# ILI9488_touch_breakout.net
KiCad netlist of a schematic drawn in EAGLE
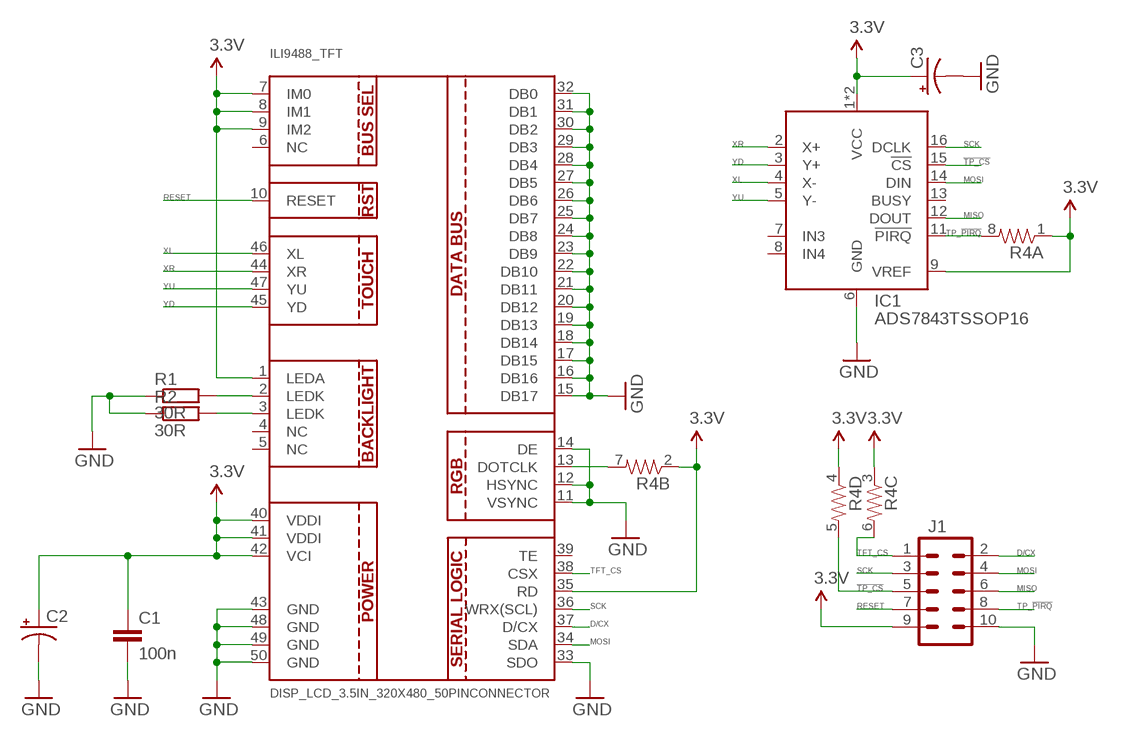
[diagram p0: schematic, sheet 1]

(export (version "E")
  (design (tool "Eeschema 10.0.6"))
  (components
    (comp (ref "C1")
      (value "100n")
      (footprint "eagle-import:C0805K")
      (libsource (lib "eagle-import") (part "C-EUC0805K"))
    )
    (comp (ref "C2")
      (value "CAPACITOR-POL0805")
      (footprint "eagle-import:0805A")
      (libsource (lib "eagle-import") (part "CAPACITOR-POL0805"))
    )
    (comp (ref "C3")
      (value "CAPACITOR-POL0805")
      (footprint "eagle-import:0805A")
      (libsource (lib "eagle-import") (part "CAPACITOR-POL0805"))
    )
    (comp (ref "IC1")
      (value "ADS7843TSSOP16")
      (footprint "eagle-import:TSSOP16")
      (libsource (lib "eagle-import") (part "ADS7843TSSOP16"))
    )
    (comp (ref "ILI9488_TFT")
      (value "DISP_LCD_3.5IN_320X480_50PINCONNECTOR")
      (footprint "eagle-import:TFT_3.5IN_50PIN_CONNECTOR")
      (libsource (lib "eagle-import") (part "DISP_LCD_3.5IN_320X480_50PINCONNECTOR"))
    )
    (comp (ref "J1")
      (value "M05X2PTH")
      (footprint "eagle-import:AVR_ICSP")
      (libsource (lib "eagle-import") (part "M05X2PTH"))
    )
    (comp (ref "R1")
      (value "30R")
      (footprint "eagle-import:M0805")
      (libsource (lib "eagle-import") (part "R-EU_M0805"))
    )
    (comp (ref "R2")
      (value "30R")
      (footprint "eagle-import:M0805")
      (libsource (lib "eagle-import") (part "R-EU_M0805"))
    )
    (comp (ref "R4")
      (value "RESISTOR-ARRAY0603-ARV")
      (footprint "eagle-import:0603-ARV")
      (libsource (lib "eagle-import") (part "RESISTOR-ARRAY0603-ARV"))
    )
  )
  (nets
    (net (code "1") (name "/D{slash}CX") (class "Default")
      (node (ref "ILI9488_TFT") (pin "37") (pinfunction "D/CX_37") (pintype "bidirectional"))
      (node (ref "J1") (pin "2") (pinfunction "2_2") (pintype "passive"))
    )
    (net (code "2") (name "/MISO") (class "Default")
      (node (ref "IC1") (pin "12") (pinfunction "DOUT_12") (pintype "bidirectional"))
      (node (ref "J1") (pin "6") (pinfunction "6_6") (pintype "passive"))
    )
    (net (code "3") (name "/MOSI") (class "Default")
      (node (ref "IC1") (pin "14") (pinfunction "DIN_14") (pintype "bidirectional"))
      (node (ref "ILI9488_TFT") (pin "34") (pinfunction "SDA_34") (pintype "bidirectional"))
      (node (ref "J1") (pin "4") (pinfunction "4_4") (pintype "passive"))
    )
    (net (code "4") (name "/RESET") (class "Default")
      (node (ref "ILI9488_TFT") (pin "10") (pinfunction "RESET_10") (pintype "bidirectional"))
      (node (ref "J1") (pin "7") (pinfunction "7_7") (pintype "passive"))
    )
    (net (code "5") (name "/SCK") (class "Default")
      (node (ref "IC1") (pin "16") (pinfunction "DCLK_16") (pintype "bidirectional"))
      (node (ref "ILI9488_TFT") (pin "36") (pinfunction "WRX(SCL)_36") (pintype "bidirectional"))
      (node (ref "J1") (pin "3") (pinfunction "3_3") (pintype "passive"))
    )
    (net (code "6") (name "/TFT_CS") (class "Default")
      (node (ref "ILI9488_TFT") (pin "38") (pinfunction "CSX_38") (pintype "bidirectional"))
      (node (ref "J1") (pin "1") (pinfunction "1_1") (pintype "passive"))
      (node (ref "R4") (pin "6") (pinfunction "2_6") (pintype "passive"))
    )
    (net (code "7") (name "/TP_~{PIRQ}") (class "Default")
      (node (ref "IC1") (pin "11") (pinfunction "~{PIRQ}_11") (pintype "bidirectional"))
      (node (ref "J1") (pin "8") (pinfunction "8_8") (pintype "passive"))
      (node (ref "R4") (pin "8") (pinfunction "2_8") (pintype "passive"))
    )
    (net (code "8") (name "/XL") (class "Default")
      (node (ref "IC1") (pin "4") (pinfunction "X-_4") (pintype "bidirectional"))
      (node (ref "ILI9488_TFT") (pin "46") (pinfunction "XL_46") (pintype "bidirectional"))
    )
    (net (code "9") (name "/XR") (class "Default")
      (node (ref "IC1") (pin "2") (pinfunction "X+_2") (pintype "bidirectional"))
      (node (ref "ILI9488_TFT") (pin "44") (pinfunction "XR_44") (pintype "bidirectional"))
    )
    (net (code "10") (name "/YD") (class "Default")
      (node (ref "IC1") (pin "3") (pinfunction "Y+_3") (pintype "bidirectional"))
      (node (ref "ILI9488_TFT") (pin "45") (pinfunction "YD_45") (pintype "bidirectional"))
    )
    (net (code "11") (name "/YU") (class "Default")
      (node (ref "IC1") (pin "5") (pinfunction "Y-_5") (pintype "bidirectional"))
      (node (ref "ILI9488_TFT") (pin "47") (pinfunction "YU_47") (pintype "bidirectional"))
    )
    (net (code "12") (name "/~{TP_CS}") (class "Default")
      (node (ref "IC1") (pin "15") (pinfunction "~{CS}_15") (pintype "bidirectional"))
      (node (ref "J1") (pin "5") (pinfunction "5_5") (pintype "passive"))
      (node (ref "R4") (pin "5") (pinfunction "2_5") (pintype "passive"))
    )
    (net (code "13") (name "3.3V") (class "Default")
      (node (ref "C1") (pin "1") (pinfunction "1_1") (pintype "passive"))
      (node (ref "C2") (pin "+") (pinfunction "+_+") (pintype "passive"))
      (node (ref "C3") (pin "+") (pinfunction "+_+") (pintype "passive"))
      (node (ref "IC1") (pin "1") (pinfunction "VCC_1") (pintype "bidirectional"))
      (node (ref "IC1") (pin "10") (pinfunction "VCC_10") (pintype "bidirectional"))
      (node (ref "IC1") (pin "9") (pinfunction "VREF_9") (pintype "bidirectional"))
      (node (ref "ILI9488_TFT") (pin "1") (pinfunction "LEDA_1") (pintype "bidirectional"))
      (node (ref "ILI9488_TFT") (pin "35") (pinfunction "RD_35") (pintype "bidirectional"))
      (node (ref "ILI9488_TFT") (pin "40") (pinfunction "VDDI_40") (pintype "bidirectional"))
      (node (ref "ILI9488_TFT") (pin "41") (pinfunction "VDDI_41") (pintype "bidirectional"))
      (node (ref "ILI9488_TFT") (pin "42") (pinfunction "VCI_42") (pintype "bidirectional"))
      (node (ref "ILI9488_TFT") (pin "7") (pinfunction "IM0_7") (pintype "bidirectional"))
      (node (ref "ILI9488_TFT") (pin "8") (pinfunction "IM1_8") (pintype "bidirectional"))
      (node (ref "ILI9488_TFT") (pin "9") (pinfunction "IM2_9") (pintype "bidirectional"))
      (node (ref "J1") (pin "9") (pinfunction "9_9") (pintype "passive"))
      (node (ref "R4") (pin "1") (pinfunction "1_1") (pintype "passive"))
      (node (ref "R4") (pin "2") (pinfunction "1_2") (pintype "passive"))
      (node (ref "R4") (pin "3") (pinfunction "1_3") (pintype "passive"))
      (node (ref "R4") (pin "4") (pinfunction "1_4") (pintype "passive"))
    )
    (net (code "14") (name "GND") (class "Default")
      (node (ref "C1") (pin "2") (pinfunction "2_2") (pintype "passive"))
      (node (ref "C2") (pin "-") (pinfunction "-_-") (pintype "passive"))
      (node (ref "C3") (pin "-") (pinfunction "-_-") (pintype "passive"))
      (node (ref "IC1") (pin "6") (pinfunction "GND_6") (pintype "bidirectional"))
      (node (ref "ILI9488_TFT") (pin "11") (pinfunction "VSYNC_11") (pintype "bidirectional"))
      (node (ref "ILI9488_TFT") (pin "12") (pinfunction "HSYNC_12") (pintype "bidirectional"))
      (node (ref "ILI9488_TFT") (pin "14") (pinfunction "DE_14") (pintype "bidirectional"))
      (node (ref "ILI9488_TFT") (pin "15") (pinfunction "DB17_15") (pintype "bidirectional"))
      (node (ref "ILI9488_TFT") (pin "16") (pinfunction "DB16_16") (pintype "bidirectional"))
      (node (ref "ILI9488_TFT") (pin "17") (pinfunction "DB15_17") (pintype "bidirectional"))
      (node (ref "ILI9488_TFT") (pin "18") (pinfunction "DB14_18") (pintype "bidirectional"))
      (node (ref "ILI9488_TFT") (pin "19") (pinfunction "DB13_19") (pintype "bidirectional"))
      (node (ref "ILI9488_TFT") (pin "20") (pinfunction "DB12_20") (pintype "bidirectional"))
      (node (ref "ILI9488_TFT") (pin "21") (pinfunction "DB11_21") (pintype "bidirectional"))
      (node (ref "ILI9488_TFT") (pin "22") (pinfunction "DB10_22") (pintype "bidirectional"))
      (node (ref "ILI9488_TFT") (pin "23") (pinfunction "DB9_23") (pintype "bidirectional"))
      (node (ref "ILI9488_TFT") (pin "24") (pinfunction "DB8_24") (pintype "bidirectional"))
      (node (ref "ILI9488_TFT") (pin "25") (pinfunction "DB7_25") (pintype "bidirectional"))
      (node (ref "ILI9488_TFT") (pin "26") (pinfunction "DB6_26") (pintype "bidirectional"))
      (node (ref "ILI9488_TFT") (pin "27") (pinfunction "DB5_27") (pintype "bidirectional"))
      (node (ref "ILI9488_TFT") (pin "28") (pinfunction "DB4_28") (pintype "bidirectional"))
      (node (ref "ILI9488_TFT") (pin "29") (pinfunction "DB3_29") (pintype "bidirectional"))
      (node (ref "ILI9488_TFT") (pin "30") (pinfunction "DB2_30") (pintype "bidirectional"))
      (node (ref "ILI9488_TFT") (pin "31") (pinfunction "DB1_31") (pintype "bidirectional"))
      (node (ref "ILI9488_TFT") (pin "32") (pinfunction "DB0_32") (pintype "bidirectional"))
      (node (ref "ILI9488_TFT") (pin "33") (pinfunction "SDO_33") (pintype "bidirectional"))
      (node (ref "ILI9488_TFT") (pin "43") (pinfunction "GND_43") (pintype "bidirectional"))
      (node (ref "ILI9488_TFT") (pin "48") (pinfunction "GND_48") (pintype "bidirectional"))
      (node (ref "ILI9488_TFT") (pin "49") (pinfunction "GND_49") (pintype "bidirectional"))
      (node (ref "ILI9488_TFT") (pin "50") (pinfunction "GND_50") (pintype "bidirectional"))
      (node (ref "J1") (pin "10") (pinfunction "10_10") (pintype "passive"))
      (node (ref "R1") (pin "1") (pinfunction "1_1") (pintype "passive"))
      (node (ref "R2") (pin "1") (pinfunction "1_1") (pintype "passive"))
    )
    (net (code "15") (name "Net-(ILI9488_TFT-DOTCLK)") (class "Default")
      (node (ref "ILI9488_TFT") (pin "13") (pinfunction "DOTCLK_13") (pintype "bidirectional"))
      (node (ref "R4") (pin "7") (pinfunction "2_7") (pintype "passive"))
    )
    (net (code "16") (name "Net-(ILI9488_TFT-LEDK-Pad2)") (class "Default")
      (node (ref "ILI9488_TFT") (pin "2") (pinfunction "LEDK_2") (pintype "bidirectional"))
      (node (ref "R1") (pin "2") (pinfunction "2_2") (pintype "passive"))
    )
    (net (code "17") (name "Net-(ILI9488_TFT-LEDK-Pad3)") (class "Default")
      (node (ref "ILI9488_TFT") (pin "3") (pinfunction "LEDK_3") (pintype "bidirectional"))
      (node (ref "R2") (pin "2") (pinfunction "2_2") (pintype "passive"))
    )
    (net (code "18") (name "unconnected-(IC1-BUSY-Pad13)") (class "Default")
      (node (ref "IC1") (pin "13") (pinfunction "BUSY_13") (pintype "bidirectional"))
    )
    (net (code "19") (name "unconnected-(IC1-IN3-Pad7)") (class "Default")
      (node (ref "IC1") (pin "7") (pinfunction "IN3_7") (pintype "bidirectional"))
    )
    (net (code "20") (name "unconnected-(IC1-IN4-Pad8)") (class "Default")
      (node (ref "IC1") (pin "8") (pinfunction "IN4_8") (pintype "bidirectional"))
    )
    (net (code "21") (name "unconnected-(ILI9488_TFT-NC-Pad4)") (class "Default")
      (node (ref "ILI9488_TFT") (pin "4") (pinfunction "NC_4") (pintype "bidirectional"))
    )
    (net (code "22") (name "unconnected-(ILI9488_TFT-NC-Pad5)") (class "Default")
      (node (ref "ILI9488_TFT") (pin "5") (pinfunction "NC_5") (pintype "bidirectional"))
    )
    (net (code "23") (name "unconnected-(ILI9488_TFT-NC-Pad6)") (class "Default")
      (node (ref "ILI9488_TFT") (pin "6") (pinfunction "NC_6") (pintype "bidirectional"))
    )
    (net (code "24") (name "unconnected-(ILI9488_TFT-TE-Pad39)") (class "Default")
      (node (ref "ILI9488_TFT") (pin "39") (pinfunction "TE_39") (pintype "bidirectional"))
    )
  )
)
